# DB4100_DRV_v0_3.net
KiCad netlist of a schematic drawn in Altium Designer
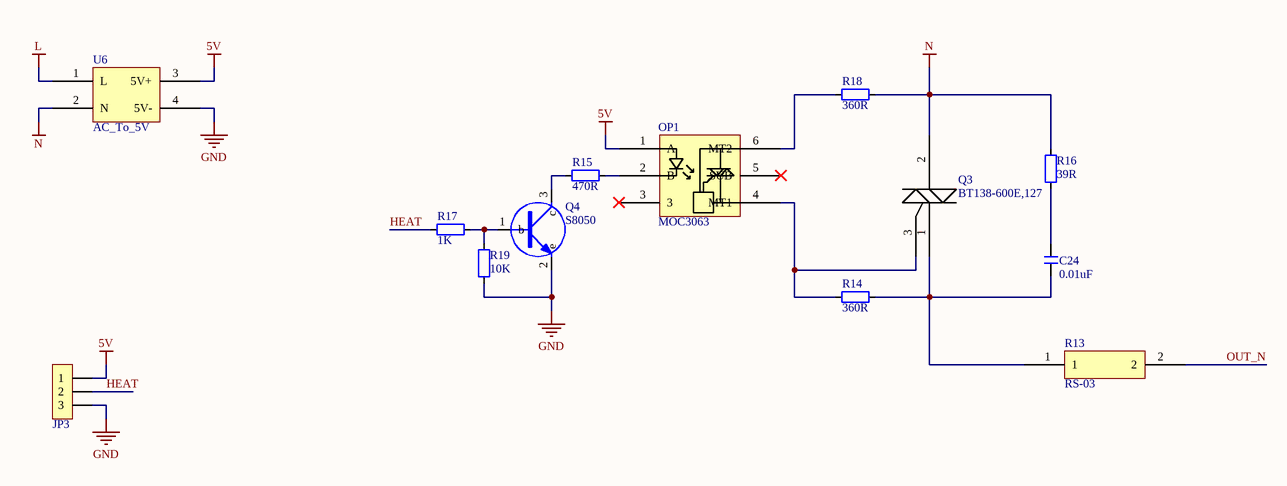
[diagram p0: DB4100_DRV_v0.3.SchDoc]

(export (version "E")
  (design (tool "Eeschema 10.0.6"))
  (components
    (comp (ref "C24")
      (value "0.01uF")
      (footprint "MLCC5.08-A")
      (description "独石电容")
      (fields (field (name "版权归属") "源创客"))
      (libsource (lib "电容") (part "C-MLCC"))
    )
    (comp (ref "JP3")
      (value "HDR-1X3")
      (footprint "XH2.54-3P")
      (description "3P接插件")
      (fields (field (name "版权归属") "源创客"))
      (libsource (lib "排针-排母") (part "Header 3"))
    )
    (comp (ref "OP1")
      (value "MOC3063")
      (footprint "MOC3063")
      (description "双向可控硅")
      (libsource (lib "常用芯片") (part "MOC3063"))
    )
    (comp (ref "Q3")
      (value "BT138-600E,127")
      (footprint "BT138-600E,127")
      (description "晶闸管(可控硅)/模块")
      (libsource (lib "二极管-整流桥") (part "BT138-600E,127"))
    )
    (comp (ref "Q4") (value "S8050") (footprint "SOT23-3L") (libsource (lib "三极管") (part "NPN")))
    (comp (ref "R13")
      (value "RS-03")
      (footprint "RS-03")
      (description "电吹风热保护器")
      (libsource (lib "模块器件") (part "RS-03"))
    )
    (comp (ref "R14")
      (value "360R")
      (footprint "R 1206")
      (description "贴片电阻")
      (fields (field (name "版权归属") "源创客"))
      (libsource (lib "") (part "R_2"))
    )
    (comp (ref "R15")
      (value "470R")
      (footprint "R 0603")
      (description "贴片电阻")
      (fields (field (name "版权归属") "源创客"))
      (libsource (lib "电阻") (part "R"))
    )
    (comp (ref "R16")
      (value "39R")
      (footprint "R 1206")
      (description "贴片电阻")
      (fields (field (name "版权归属") "源创客"))
      (libsource (lib "") (part "R_1"))
    )
    (comp (ref "R17")
      (value "1K")
      (footprint "R 0603")
      (description "贴片电阻")
      (fields (field (name "版权归属") "源创客"))
      (libsource (lib "电阻") (part "R"))
    )
    (comp (ref "R18")
      (value "360R")
      (footprint "R 1206")
      (description "贴片电阻")
      (fields (field (name "版权归属") "源创客"))
      (libsource (lib "") (part "R_2"))
    )
    (comp (ref "R19")
      (value "10K")
      (footprint "R 0603")
      (description "贴片电阻")
      (fields (field (name "版权归属") "源创客"))
      (libsource (lib "") (part "R_2"))
    )
    (comp (ref "U6")
      (value "AC_To_5V")
      (footprint "ACTo5v")
      (description "220V转5V降压模块")
      (libsource (lib "变压器") (part "AC_To_5V"))
    )
  )
  (nets
    (net (code "1") (name "/HEAT") (class "Default")
      (node (ref "JP3") (pin "2") (pinfunction "2_2") (pintype "passive"))
      (node (ref "R17") (pin "1") (pinfunction "1_1") (pintype "passive"))
    )
    (net (code "2") (name "/OUT_N") (class "Default")
      (node (ref "R13") (pin "2") (pinfunction "2_2") (pintype "passive"))
    )
    (net (code "3") (name "5V") (class "Default")
      (node (ref "JP3") (pin "1") (pinfunction "1_1") (pintype "passive"))
      (node (ref "OP1") (pin "1") (pinfunction "A_1") (pintype "passive"))
      (node (ref "U6") (pin "3") (pinfunction "5V+_3") (pintype "passive"))
    )
    (net (code "4") (name "GND") (class "Default")
      (node (ref "JP3") (pin "3") (pinfunction "3_3") (pintype "passive"))
      (node (ref "Q4") (pin "2") (pinfunction "e_2") (pintype "passive"))
      (node (ref "R19") (pin "1") (pinfunction "1_1") (pintype "passive"))
      (node (ref "U6") (pin "4") (pinfunction "5V-_4") (pintype "passive"))
    )
    (net (code "5") (name "L") (class "Default")
      (node (ref "U6") (pin "1") (pinfunction "L_1") (pintype "passive"))
    )
    (net (code "6") (name "N") (class "Default")
      (node (ref "Q3") (pin "2") (pinfunction "2_2") (pintype "passive"))
      (node (ref "R16") (pin "1") (pinfunction "1_1") (pintype "passive"))
      (node (ref "R18") (pin "2") (pinfunction "2_2") (pintype "passive"))
      (node (ref "U6") (pin "2") (pinfunction "N_2") (pintype "passive"))
    )
    (net (code "7") (name "Net-(C24-Pad1)") (class "Default")
      (node (ref "C24") (pin "1") (pinfunction "1_1") (pintype "passive"))
      (node (ref "R16") (pin "2") (pinfunction "2_2") (pintype "passive"))
    )
    (net (code "8") (name "Net-(C24-Pad2)") (class "Default")
      (node (ref "C24") (pin "2") (pinfunction "2_2") (pintype "passive"))
      (node (ref "Q3") (pin "1") (pinfunction "1_1") (pintype "passive"))
      (node (ref "R13") (pin "1") (pinfunction "1_1") (pintype "passive"))
      (node (ref "R14") (pin "2") (pinfunction "2_2") (pintype "passive"))
    )
    (net (code "9") (name "Net-(OP1-B)") (class "Default")
      (node (ref "OP1") (pin "2") (pinfunction "B_2") (pintype "passive"))
      (node (ref "R15") (pin "2") (pinfunction "2_2") (pintype "passive"))
    )
    (net (code "10") (name "Net-(OP1-MT1)") (class "Default")
      (node (ref "OP1") (pin "4") (pinfunction "MT1_4") (pintype "passive"))
      (node (ref "Q3") (pin "3") (pinfunction "3_3") (pintype "passive"))
      (node (ref "R14") (pin "1") (pinfunction "1_1") (pintype "passive"))
    )
    (net (code "11") (name "Net-(OP1-MT2)") (class "Default")
      (node (ref "OP1") (pin "6") (pinfunction "MT2_6") (pintype "passive"))
      (node (ref "R18") (pin "1") (pinfunction "1_1") (pintype "passive"))
    )
    (net (code "12") (name "Net-(Q4-b)") (class "Default")
      (node (ref "Q4") (pin "1") (pinfunction "b_1") (pintype "passive"))
      (node (ref "R17") (pin "2") (pinfunction "2_2") (pintype "passive"))
      (node (ref "R19") (pin "2") (pinfunction "2_2") (pintype "passive"))
    )
    (net (code "13") (name "Net-(Q4-c)") (class "Default")
      (node (ref "Q4") (pin "3") (pinfunction "c_3") (pintype "passive"))
      (node (ref "R15") (pin "1") (pinfunction "1_1") (pintype "passive"))
    )
    (net (code "14") (name "unconnected-(OP1-Pad3)") (class "Default")
      (node (ref "OP1") (pin "3") (pinfunction "3_3") (pintype "passive+no_connect"))
    )
    (net (code "15") (name "unconnected-(OP1-SUB-Pad5)") (class "Default")
      (node (ref "OP1") (pin "5") (pinfunction "SUB_5") (pintype "passive+no_connect"))
    )
  )
)
